# ETH.net
KiCad netlist of a schematic drawn in Altium Designer
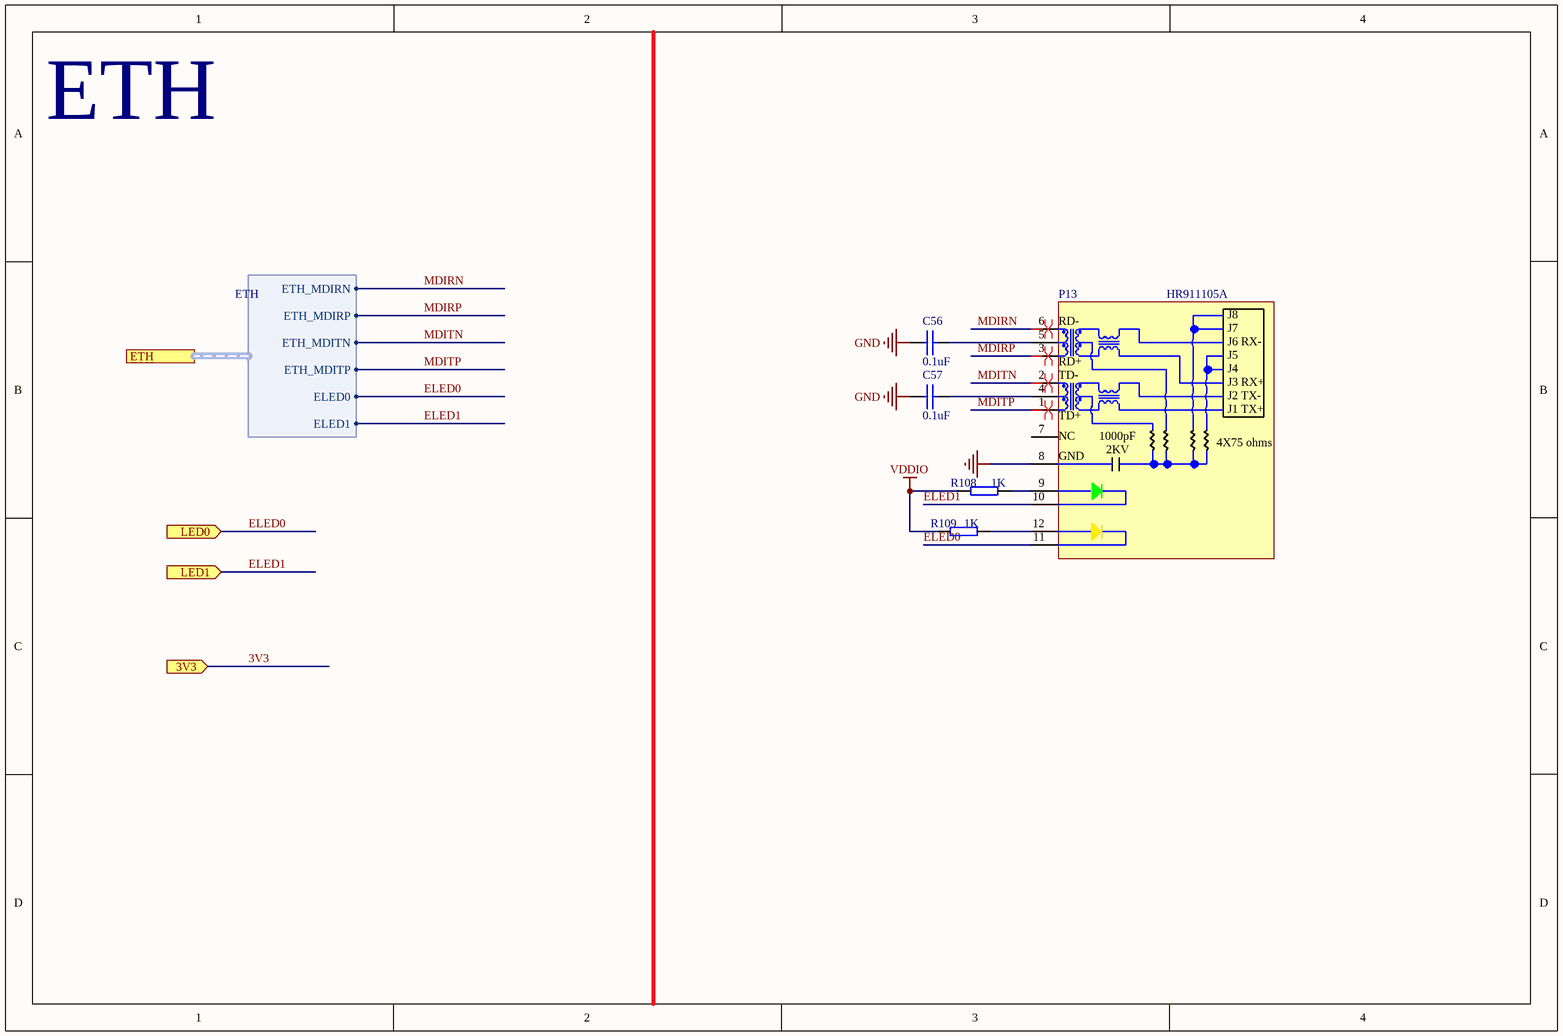
[diagram p0: ETH.SchDoc]

(export (version "E")
  (design (tool "Eeschema 10.0.6"))
  (components
    (comp (ref "C56")
      (value "0.1uF")
      (footprint "0402_C")
      (description "Capacitor")
      (libsource (lib "wch_sch_others") (part "CAP"))
    )
    (comp (ref "C57")
      (value "0.1uF")
      (footprint "0402_C")
      (description "Capacitor")
      (libsource (lib "wch_sch_others") (part "CAP"))
    )
    (comp (ref "P13") (value "HR911105A") (footprint "HR911105A") (libsource (lib "*") (part "HR911105A")))
    (comp (ref "R108") (value "1K") (footprint "0402") (libsource (lib "wch_sch_others") (part "RES")))
    (comp (ref "R109") (value "1K") (footprint "0402") (libsource (lib "wch_sch_others") (part "RES")))
  )
  (nets
    (net (code "3") (name "/ELED0") (class "Default") (node (ref "P13") (pin "11") (pintype "passive")))
    (net (code "4") (name "/ELED1") (class "Default") (node (ref "P13") (pin "10") (pintype "passive")))
    (net (code "5") (name "/MDIRN") (class "Default") (node (ref "P13") (pin "6") (pintype "passive")))
    (net (code "6") (name "/MDIRP") (class "Default") (node (ref "P13") (pin "3") (pintype "passive")))
    (net (code "7") (name "/MDITN") (class "Default") (node (ref "P13") (pin "2") (pintype "passive")))
    (net (code "8") (name "/MDITP") (class "Default") (node (ref "P13") (pin "1") (pintype "passive")))
    (net (code "10") (name "GND") (class "Default")
      (node (ref "C56") (pin "1") (pinfunction "1_1") (pintype "passive"))
      (node (ref "C57") (pin "1") (pinfunction "1_1") (pintype "passive"))
      (node (ref "P13") (pin "8") (pintype "passive"))
    )
    (net (code "11") (name "Net-(C56-Pad2)") (class "Default")
      (node (ref "C56") (pin "2") (pinfunction "2_2") (pintype "passive"))
      (node (ref "P13") (pin "5") (pintype "passive"))
    )
    (net (code "12") (name "Net-(C57-Pad2)") (class "Default")
      (node (ref "C57") (pin "2") (pinfunction "2_2") (pintype "passive"))
      (node (ref "P13") (pin "4") (pintype "passive"))
    )
    (net (code "13") (name "Net-(P13-Pad9)") (class "Default")
      (node (ref "P13") (pin "9") (pintype "passive"))
      (node (ref "R108") (pin "2") (pintype "passive"))
    )
    (net (code "14") (name "Net-(P13-Pad12)") (class "Default")
      (node (ref "P13") (pin "12") (pintype "passive"))
      (node (ref "R109") (pin "2") (pintype "passive"))
    )
    (net (code "15") (name "VDDIO") (class "Default")
      (node (ref "R108") (pin "1") (pintype "passive"))
      (node (ref "R109") (pin "1") (pintype "passive"))
    )
    (net (code "16") (name "unconnected-(P13-Pad7)") (class "Default")
      (node (ref "P13") (pin "7") (pintype "passive"))
    )
  )
)
